# 2_MCU.net
KiCad netlist of a schematic drawn in Altium Designer
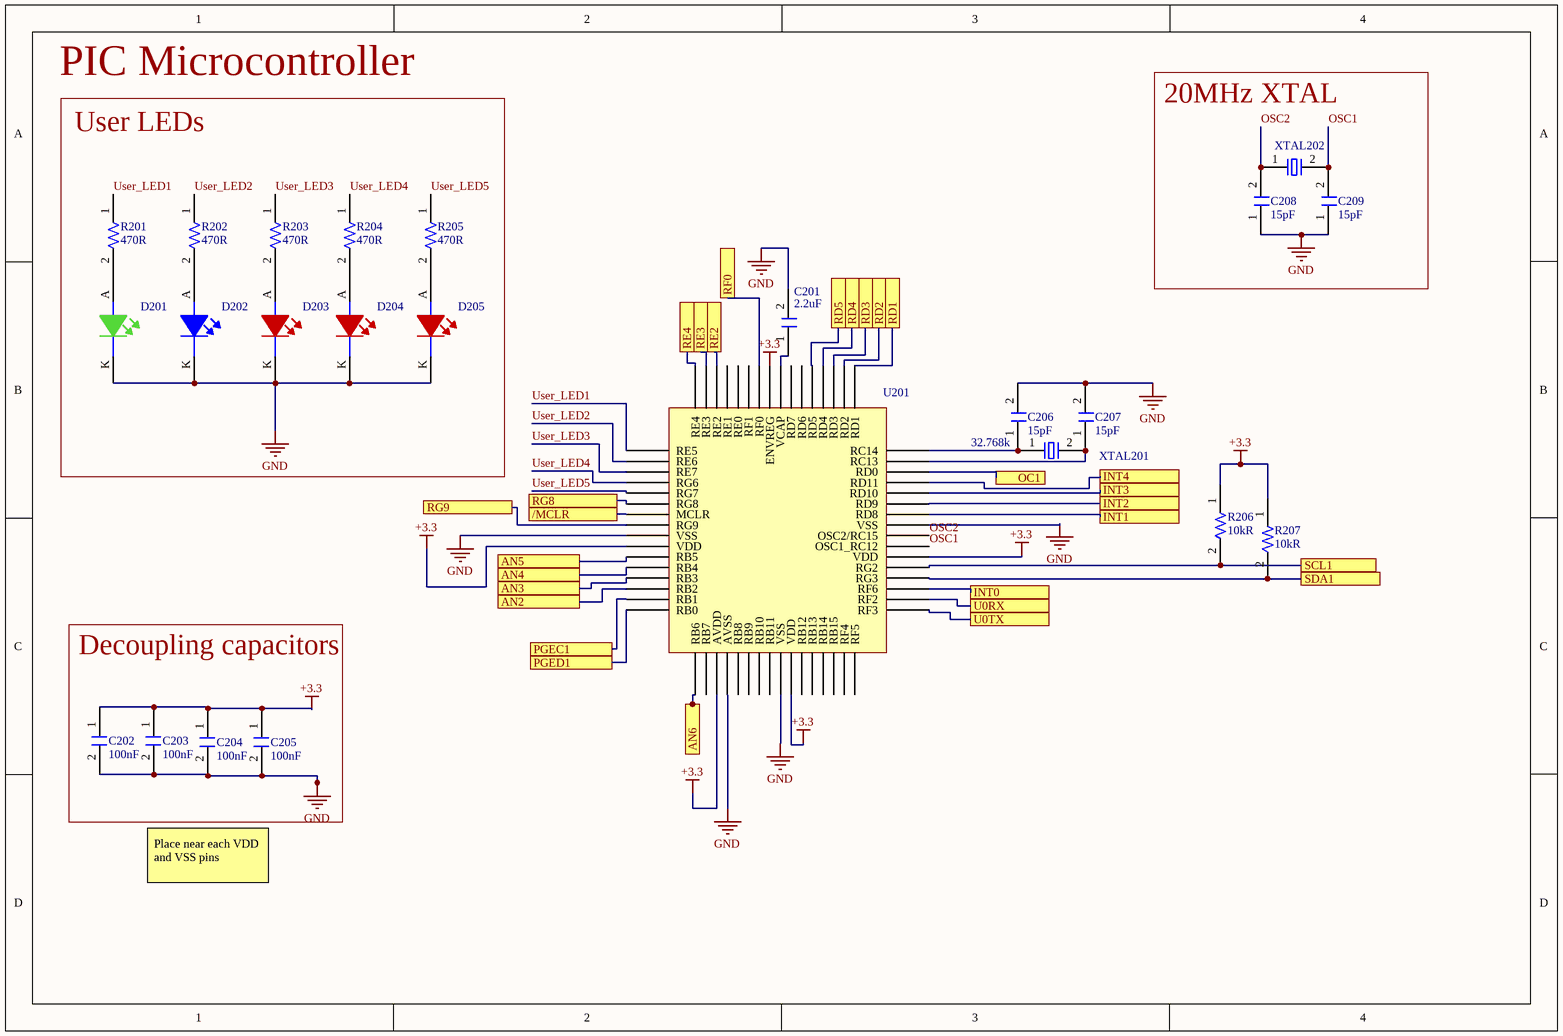
[diagram p0: [2]MCU.SchDoc]

(export (version "E")
  (design (tool "Eeschema 10.0.6"))
  (components
    (comp (ref "C201")
      (value "2.2uF")
      (footprint "C0805FNPC-W")
      (libsource (lib "Passives") (part "C2.2u-16V-0805FTK"))
    )
    (comp (ref "C202")
      (value "885012207098")
      (footprint "C0805FNPC-R")
      (description "Cap, 0.1ΜF, 50V, 10%, X7R, 0805")
      (fields
        (field (name "TOLERANCE") "10%")
        (field (name "CAPACITANCE") "100nF")
        (field (name ".CREATOR") "DR")
      )
      (libsource (lib "Passives") (part "C100n-50V-0805FNPC-X7R"))
    )
    (comp (ref "C203")
      (value "885012207098")
      (footprint "C0805FNPC-R")
      (description "Cap, 0.1ΜF, 50V, 10%, X7R, 0805")
      (fields
        (field (name "TOLERANCE") "10%")
        (field (name "CAPACITANCE") "100nF")
        (field (name ".CREATOR") "DR")
      )
      (libsource (lib "Passives") (part "C100n-50V-0805FNPC-X7R"))
    )
    (comp (ref "C204")
      (value "885012207098")
      (footprint "C0805FNPC-R")
      (description "Cap, 0.1ΜF, 50V, 10%, X7R, 0805")
      (fields
        (field (name "TOLERANCE") "10%")
        (field (name "CAPACITANCE") "100nF")
        (field (name ".CREATOR") "DR")
      )
      (libsource (lib "Passives") (part "C100n-50V-0805FNPC-X7R"))
    )
    (comp (ref "C205")
      (value "885012207098")
      (footprint "C0805FNPC-R")
      (description "Cap, 0.1ΜF, 50V, 10%, X7R, 0805")
      (fields
        (field (name "TOLERANCE") "10%")
        (field (name "CAPACITANCE") "100nF")
        (field (name ".CREATOR") "DR")
      )
      (libsource (lib "Passives") (part "C100n-50V-0805FNPC-X7R"))
    )
    (comp (ref "C206")
      (value "885012008038")
      (footprint "C1206FNPC-RW")
      (description "Cap, 15Pf, 50V, 5%, C0G/np0, 1206 Rohs Compliant: Yes")
      (fields
        (field (name "MANUFACTURER") "Wurth Electronics")
        (field (name "TOLERANCE") "5%")
        (field (name "CAPACITANCE") "15pF")
        (field (name ".CREATOR") "GP")
      )
      (libsource (lib "Passives") (part "C15p-50V-1206FNPC-NP0"))
    )
    (comp (ref "C207")
      (value "885012008038")
      (footprint "C1206FNPC-RW")
      (description "Cap, 15Pf, 50V, 5%, C0G/np0, 1206 Rohs Compliant: Yes")
      (fields
        (field (name "MANUFACTURER") "Wurth Electronics")
        (field (name "TOLERANCE") "5%")
        (field (name "CAPACITANCE") "15pF")
        (field (name ".CREATOR") "GP")
      )
      (libsource (lib "Passives") (part "C15p-50V-1206FNPC-NP0"))
    )
    (comp (ref "C208")
      (value "885012008038")
      (footprint "C1206FNPC-RW")
      (description "Cap, 15Pf, 50V, 5%, C0G/np0, 1206 Rohs Compliant: Yes")
      (fields
        (field (name "MANUFACTURER") "Wurth Electronics")
        (field (name "TOLERANCE") "5%")
        (field (name "CAPACITANCE") "15pF")
        (field (name ".CREATOR") "GP")
      )
      (libsource (lib "Passives") (part "C15p-50V-1206FNPC-NP0"))
    )
    (comp (ref "C209")
      (value "885012008038")
      (footprint "C1206FNPC-RW")
      (description "Cap, 15Pf, 50V, 5%, C0G/np0, 1206 Rohs Compliant: Yes")
      (fields
        (field (name "MANUFACTURER") "Wurth Electronics")
        (field (name "TOLERANCE") "5%")
        (field (name "CAPACITANCE") "15pF")
        (field (name ".CREATOR") "GP")
      )
      (libsource (lib "Passives") (part "C15p-50V-1206FNPC-NP0"))
    )
    (comp (ref "D201")
      (value "150080VS75000")
      (footprint "LED_0805_WE")
      (description "Led, Green, 570 Nm, 2 V, 30 Ma, 40 Mcd Rohs Compliant: Yes")
      (fields (field (name ".CREATOR") "DR"))
      (libsource (lib "Semiconductor") (part "LEDVS-0805-40"))
    )
    (comp (ref "D202")
      (value "150080BS75000")
      (footprint "LED_0805_WE")
      (description "LED BLUE CLEAR 0805 SMD")
      (fields (field (name ".CREATOR") "GP"))
      (libsource (lib "Semiconductor") (part "LEDBS-0805-145"))
    )
    (comp (ref "D203")
      (value "150080RS75000")
      (footprint "LED_0805_WE")
      (description "0805(H=0.8mm) 红色 高亮 λD=625nm VF=2V IF=30mA PD=72mW")
      (fields (field (name ".CREATOR") "DR"))
      (libsource (lib "Semiconductor") (part "LEDRS-0805-150"))
    )
    (comp (ref "D204")
      (value "150080RS75000")
      (footprint "LED_0805_WE")
      (description "0805(H=0.8mm) 红色 高亮 λD=625nm VF=2V IF=30mA PD=72mW")
      (fields (field (name ".CREATOR") "DR"))
      (libsource (lib "Semiconductor") (part "LEDRS-0805-150"))
    )
    (comp (ref "D205")
      (value "150080RS75000")
      (footprint "LED_0805_WE")
      (description "0805(H=0.8mm) 红色 高亮 λD=625nm VF=2V IF=30mA PD=72mW")
      (fields (field (name ".CREATOR") "DR"))
      (libsource (lib "Semiconductor") (part "LEDRS-0805-150"))
    )
    (comp (ref "R201")
      (value "CR0805-FX-4700GLF")
      (footprint "R0805FTK")
      (description "Res Thick Film 0805 470 Ohm 1% 1/8W ±100ppm/°C Molded SMD SMD Paper Tape on Plastic Reel")
      (fields
        (field (name "TOLERANCE") "1%")
        (field (name "RESISTANCE") "470R")
        (field (name ".CREATOR") "DR")
      )
      (libsource (lib "Passives") (part "R470-0805FTK"))
    )
    (comp (ref "R202")
      (value "CR0805-FX-4700GLF")
      (footprint "R0805FTK")
      (description "Res Thick Film 0805 470 Ohm 1% 1/8W ±100ppm/°C Molded SMD SMD Paper Tape on Plastic Reel")
      (fields
        (field (name "TOLERANCE") "1%")
        (field (name "RESISTANCE") "470R")
        (field (name ".CREATOR") "DR")
      )
      (libsource (lib "Passives") (part "R470-0805FTK"))
    )
    (comp (ref "R203")
      (value "CR0805-FX-4700GLF")
      (footprint "R0805FTK")
      (description "Res Thick Film 0805 470 Ohm 1% 1/8W ±100ppm/°C Molded SMD SMD Paper Tape on Plastic Reel")
      (fields
        (field (name "TOLERANCE") "1%")
        (field (name "RESISTANCE") "470R")
        (field (name ".CREATOR") "DR")
      )
      (libsource (lib "Passives") (part "R470-0805FTK"))
    )
    (comp (ref "R204")
      (value "CR0805-FX-4700GLF")
      (footprint "R0805FTK")
      (description "Res Thick Film 0805 470 Ohm 1% 1/8W ±100ppm/°C Molded SMD SMD Paper Tape on Plastic Reel")
      (fields
        (field (name "TOLERANCE") "1%")
        (field (name "RESISTANCE") "470R")
        (field (name ".CREATOR") "DR")
      )
      (libsource (lib "Passives") (part "R470-0805FTK"))
    )
    (comp (ref "R205")
      (value "CR0805-FX-4700GLF")
      (footprint "R0805FTK")
      (description "Res Thick Film 0805 470 Ohm 1% 1/8W ±100ppm/°C Molded SMD SMD Paper Tape on Plastic Reel")
      (fields
        (field (name "TOLERANCE") "1%")
        (field (name "RESISTANCE") "470R")
        (field (name ".CREATOR") "DR")
      )
      (libsource (lib "Passives") (part "R470-0805FTK"))
    )
    (comp (ref "R206")
      (value "CR0805-JW-103ELF")
      (footprint "R0805FTK")
      (fields
        (field (name "TOLERANCE") "5%")
        (field (name "RESISTANCE") "10kR")
        (field (name ".CREATOR") "DR")
      )
      (libsource (lib "Passives") (part "R10k-0805FTK"))
    )
    (comp (ref "R207")
      (value "CR0805-JW-103ELF")
      (footprint "R0805FTK")
      (fields
        (field (name "TOLERANCE") "5%")
        (field (name "RESISTANCE") "10kR")
        (field (name ".CREATOR") "DR")
      )
      (libsource (lib "Passives") (part "R10k-0805FTK"))
    )
    (comp (ref "U201")
      (value "PIC32MX340F512H")
      (footprint "QFP50P1200X1200X120_64N")
      (libsource (lib "CommonFiles_Library") (part "PIC32MX340F512H"))
    )
    (comp (ref "XTAL201")
      (value "32.768k")
      (footprint "XTAL_ABS06-32.768KHZ-9-T")
      (libsource (lib "CommonFiles_Library") (part "XTAL_SMD_32.768kHz"))
    )
    (comp (ref "XTAL202")
      (value "830028710")
      (footprint "XTAL20M_SMD")
      (description "830028710, 20 MHz")
      (fields (field (name "MANUFACTURER") "Würth Elektronik") (field (name ".CREATOR") "GP"))
      (libsource (lib "Passives") (part "XTAL20M_SMD"))
    )
  )
  (nets
    (net (code "1") (name "+3.3") (class "Default")
      (node (ref "C202") (pin "1") (pinfunction "1_1") (pintype "passive"))
      (node (ref "C203") (pin "1") (pinfunction "1_1") (pintype "passive"))
      (node (ref "C204") (pin "1") (pinfunction "1_1") (pintype "passive"))
      (node (ref "C205") (pin "1") (pinfunction "1_1") (pintype "passive"))
      (node (ref "R206") (pin "1") (pinfunction "1_1") (pintype "passive"))
      (node (ref "R207") (pin "1") (pinfunction "1_1") (pintype "passive"))
      (node (ref "U201") (pin "10") (pinfunction "VDD_10") (pintype "passive"))
      (node (ref "U201") (pin "19") (pinfunction "AVDD_19") (pintype "passive"))
      (node (ref "U201") (pin "26") (pinfunction "VDD_26") (pintype "passive"))
      (node (ref "U201") (pin "38") (pinfunction "VDD_38") (pintype "passive"))
      (node (ref "U201") (pin "57") (pinfunction "ENVREG_57") (pintype "passive"))
    )
    (net (code "2") (name "/AN2") (class "Default")
      (node (ref "U201") (pin "14") (pinfunction "RB2_14") (pintype "passive"))
    )
    (net (code "3") (name "/AN3") (class "Default")
      (node (ref "U201") (pin "13") (pinfunction "RB3_13") (pintype "passive"))
    )
    (net (code "4") (name "/AN4") (class "Default")
      (node (ref "U201") (pin "12") (pinfunction "RB4_12") (pintype "passive"))
    )
    (net (code "5") (name "/AN5") (class "Default")
      (node (ref "U201") (pin "11") (pinfunction "RB5_11") (pintype "passive"))
    )
    (net (code "6") (name "/AN6") (class "Default")
      (node (ref "U201") (pin "17") (pinfunction "RB6_17") (pintype "passive"))
    )
    (net (code "7") (name "/INT0") (class "Default")
      (node (ref "U201") (pin "35") (pinfunction "RF6_35") (pintype "passive"))
    )
    (net (code "8") (name "/INT1") (class "Default")
      (node (ref "U201") (pin "42") (pinfunction "RD8_42") (pintype "passive"))
    )
    (net (code "9") (name "/INT2") (class "Default")
      (node (ref "U201") (pin "43") (pinfunction "RD9_43") (pintype "passive"))
    )
    (net (code "10") (name "/INT3") (class "Default")
      (node (ref "U201") (pin "44") (pinfunction "RD10_44") (pintype "passive"))
    )
    (net (code "11") (name "/INT4") (class "Default")
      (node (ref "U201") (pin "45") (pinfunction "RD11_45") (pintype "passive"))
    )
    (net (code "12") (name "/OC1") (class "Default")
      (node (ref "U201") (pin "46") (pinfunction "RD0_46") (pintype "passive"))
    )
    (net (code "13") (name "/OSC1") (class "Default")
      (node (ref "C209") (pin "2") (pinfunction "2_2") (pintype "passive"))
      (node (ref "U201") (pin "39") (pinfunction "OSC1_RC12_39") (pintype "passive"))
      (node (ref "XTAL202") (pin "2") (pinfunction "2_2") (pintype "passive"))
    )
    (net (code "14") (name "/OSC2") (class "Default")
      (node (ref "C208") (pin "2") (pinfunction "2_2") (pintype "passive"))
      (node (ref "U201") (pin "40") (pinfunction "OSC2/RC15_40") (pintype "passive"))
      (node (ref "XTAL202") (pin "1") (pinfunction "1_1") (pintype "passive"))
    )
    (net (code "15") (name "/PGEC1") (class "Default")
      (node (ref "U201") (pin "15") (pinfunction "RB1_15") (pintype "passive"))
    )
    (net (code "16") (name "/PGED1") (class "Default")
      (node (ref "U201") (pin "16") (pinfunction "RB0_16") (pintype "passive"))
    )
    (net (code "17") (name "/RD1") (class "Default")
      (node (ref "U201") (pin "49") (pinfunction "RD1_49") (pintype "passive"))
    )
    (net (code "18") (name "/RD2") (class "Default")
      (node (ref "U201") (pin "50") (pinfunction "RD2_50") (pintype "passive"))
    )
    (net (code "19") (name "/RD3") (class "Default")
      (node (ref "U201") (pin "51") (pinfunction "RD3_51") (pintype "passive"))
    )
    (net (code "20") (name "/RD4") (class "Default")
      (node (ref "U201") (pin "52") (pinfunction "RD4_52") (pintype "passive"))
    )
    (net (code "21") (name "/RD5") (class "Default")
      (node (ref "U201") (pin "53") (pinfunction "RD5_53") (pintype "passive"))
    )
    (net (code "22") (name "/RE2") (class "Default")
      (node (ref "U201") (pin "62") (pinfunction "RE2_62") (pintype "passive"))
    )
    (net (code "23") (name "/RE3") (class "Default")
      (node (ref "U201") (pin "63") (pinfunction "RE3_63") (pintype "passive"))
    )
    (net (code "24") (name "/RE4") (class "Default")
      (node (ref "U201") (pin "64") (pinfunction "RE4_64") (pintype "passive"))
    )
    (net (code "25") (name "/RF0") (class "Default")
      (node (ref "U201") (pin "58") (pinfunction "RF0_58") (pintype "passive"))
    )
    (net (code "26") (name "/RG8") (class "Default")
      (node (ref "U201") (pin "6") (pinfunction "RG8_6") (pintype "passive"))
    )
    (net (code "27") (name "/RG9") (class "Default")
      (node (ref "U201") (pin "8") (pinfunction "RG9_8") (pintype "passive"))
    )
    (net (code "28") (name "/SCL1") (class "Default")
      (node (ref "R206") (pin "2") (pinfunction "2_2") (pintype "passive"))
      (node (ref "U201") (pin "37") (pinfunction "RG2_37") (pintype "passive"))
    )
    (net (code "29") (name "/SDA1") (class "Default")
      (node (ref "R207") (pin "2") (pinfunction "2_2") (pintype "passive"))
      (node (ref "U201") (pin "36") (pinfunction "RG3_36") (pintype "passive"))
    )
    (net (code "30") (name "/U0RX") (class "Default")
      (node (ref "U201") (pin "34") (pinfunction "RF2_34") (pintype "passive"))
    )
    (net (code "31") (name "/U0TX") (class "Default")
      (node (ref "U201") (pin "33") (pinfunction "RF3_33") (pintype "passive"))
    )
    (net (code "32") (name "/User_LED1") (class "Default")
      (node (ref "R201") (pin "1") (pinfunction "1_1") (pintype "passive"))
      (node (ref "U201") (pin "1") (pinfunction "RE5_1") (pintype "passive"))
    )
    (net (code "33") (name "/User_LED2") (class "Default")
      (node (ref "R202") (pin "1") (pinfunction "1_1") (pintype "passive"))
      (node (ref "U201") (pin "2") (pinfunction "RE6_2") (pintype "passive"))
    )
    (net (code "34") (name "/User_LED3") (class "Default")
      (node (ref "R203") (pin "1") (pinfunction "1_1") (pintype "passive"))
      (node (ref "U201") (pin "3") (pinfunction "RE7_3") (pintype "passive"))
    )
    (net (code "35") (name "/User_LED4") (class "Default")
      (node (ref "R204") (pin "1") (pinfunction "1_1") (pintype "passive"))
      (node (ref "U201") (pin "4") (pinfunction "RG6_4") (pintype "passive"))
    )
    (net (code "36") (name "/User_LED5") (class "Default")
      (node (ref "R205") (pin "1") (pinfunction "1_1") (pintype "passive"))
      (node (ref "U201") (pin "5") (pinfunction "RG7_5") (pintype "passive"))
    )
    (net (code "37") (name "/{slash}MCLR") (class "Default")
      (node (ref "U201") (pin "7") (pinfunction "MCLR_7") (pintype "passive"))
    )
    (net (code "38") (name "GND") (class "Default")
      (node (ref "C201") (pin "2") (pinfunction "2_2") (pintype "passive"))
      (node (ref "C202") (pin "2") (pinfunction "2_2") (pintype "passive"))
      (node (ref "C203") (pin "2") (pinfunction "2_2") (pintype "passive"))
      (node (ref "C204") (pin "2") (pinfunction "2_2") (pintype "passive"))
      (node (ref "C205") (pin "2") (pinfunction "2_2") (pintype "passive"))
      (node (ref "C206") (pin "2") (pinfunction "2_2") (pintype "passive"))
      (node (ref "C207") (pin "2") (pinfunction "2_2") (pintype "passive"))
      (node (ref "C208") (pin "1") (pinfunction "1_1") (pintype "passive"))
      (node (ref "C209") (pin "1") (pinfunction "1_1") (pintype "passive"))
      (node (ref "D201") (pin "K") (pinfunction "K_K") (pintype "passive"))
      (node (ref "D202") (pin "K") (pinfunction "K_K") (pintype "passive"))
      (node (ref "D203") (pin "K") (pinfunction "K_K") (pintype "passive"))
      (node (ref "D204") (pin "K") (pinfunction "K_K") (pintype "passive"))
      (node (ref "D205") (pin "K") (pinfunction "K_K") (pintype "passive"))
      (node (ref "U201") (pin "20") (pinfunction "AVSS_20") (pintype "passive"))
      (node (ref "U201") (pin "25") (pinfunction "VSS_25") (pintype "passive"))
      (node (ref "U201") (pin "41") (pinfunction "VSS_41") (pintype "passive"))
      (node (ref "U201") (pin "9") (pinfunction "VSS_9") (pintype "passive"))
    )
    (net (code "39") (name "Net-(D201-PadA)") (class "Default")
      (node (ref "D201") (pin "A") (pinfunction "A_A") (pintype "passive"))
      (node (ref "R201") (pin "2") (pinfunction "2_2") (pintype "passive"))
    )
    (net (code "40") (name "Net-(D202-PadA)") (class "Default")
      (node (ref "D202") (pin "A") (pinfunction "A_A") (pintype "passive"))
      (node (ref "R202") (pin "2") (pinfunction "2_2") (pintype "passive"))
    )
    (net (code "41") (name "Net-(D203-PadA)") (class "Default")
      (node (ref "D203") (pin "A") (pinfunction "A_A") (pintype "passive"))
      (node (ref "R203") (pin "2") (pinfunction "2_2") (pintype "passive"))
    )
    (net (code "42") (name "Net-(D204-PadA)") (class "Default")
      (node (ref "D204") (pin "A") (pinfunction "A_A") (pintype "passive"))
      (node (ref "R204") (pin "2") (pinfunction "2_2") (pintype "passive"))
    )
    (net (code "43") (name "Net-(D205-PadA)") (class "Default")
      (node (ref "D205") (pin "A") (pinfunction "A_A") (pintype "passive"))
      (node (ref "R205") (pin "2") (pinfunction "2_2") (pintype "passive"))
    )
    (net (code "44") (name "Net-(U201-RC13)") (class "Default")
      (node (ref "C207") (pin "1") (pinfunction "1_1") (pintype "passive"))
      (node (ref "U201") (pin "47") (pinfunction "RC13_47") (pintype "passive"))
      (node (ref "XTAL201") (pin "2") (pinfunction "2_2") (pintype "passive"))
    )
    (net (code "45") (name "Net-(U201-RC14)") (class "Default")
      (node (ref "C206") (pin "1") (pinfunction "1_1") (pintype "passive"))
      (node (ref "U201") (pin "48") (pinfunction "RC14_48") (pintype "passive"))
      (node (ref "XTAL201") (pin "1") (pinfunction "1_1") (pintype "passive"))
    )
    (net (code "46") (name "Net-(U201-VCAP)") (class "Default")
      (node (ref "C201") (pin "1") (pinfunction "1_1") (pintype "passive"))
      (node (ref "U201") (pin "56") (pinfunction "VCAP_56") (pintype "passive"))
    )
    (net (code "47") (name "unconnected-(U201-RB7-Pad18)") (class "Default")
      (node (ref "U201") (pin "18") (pinfunction "RB7_18") (pintype "passive"))
    )
    (net (code "48") (name "unconnected-(U201-RB8-Pad21)") (class "Default")
      (node (ref "U201") (pin "21") (pinfunction "RB8_21") (pintype "passive"))
    )
    (net (code "49") (name "unconnected-(U201-RB9-Pad22)") (class "Default")
      (node (ref "U201") (pin "22") (pinfunction "RB9_22") (pintype "passive"))
    )
    (net (code "50") (name "unconnected-(U201-RB10-Pad23)") (class "Default")
      (node (ref "U201") (pin "23") (pinfunction "RB10_23") (pintype "passive"))
    )
    (net (code "51") (name "unconnected-(U201-RB11-Pad24)") (class "Default")
      (node (ref "U201") (pin "24") (pinfunction "RB11_24") (pintype "passive"))
    )
    (net (code "52") (name "unconnected-(U201-RB12-Pad27)") (class "Default")
      (node (ref "U201") (pin "27") (pinfunction "RB12_27") (pintype "passive"))
    )
    (net (code "53") (name "unconnected-(U201-RB13-Pad28)") (class "Default")
      (node (ref "U201") (pin "28") (pinfunction "RB13_28") (pintype "passive"))
    )
    (net (code "54") (name "unconnected-(U201-RB14-Pad29)") (class "Default")
      (node (ref "U201") (pin "29") (pinfunction "RB14_29") (pintype "passive"))
    )
    (net (code "55") (name "unconnected-(U201-RB15-Pad30)") (class "Default")
      (node (ref "U201") (pin "30") (pinfunction "RB15_30") (pintype "passive"))
    )
    (net (code "56") (name "unconnected-(U201-RD6-Pad54)") (class "Default")
      (node (ref "U201") (pin "54") (pinfunction "RD6_54") (pintype "passive"))
    )
    (net (code "57") (name "unconnected-(U201-RD7-Pad55)") (class "Default")
      (node (ref "U201") (pin "55") (pinfunction "RD7_55") (pintype "passive"))
    )
    (net (code "58") (name "unconnected-(U201-RE0-Pad60)") (class "Default")
      (node (ref "U201") (pin "60") (pinfunction "RE0_60") (pintype "passive"))
    )
    (net (code "59") (name "unconnected-(U201-RE1-Pad61)") (class "Default")
      (node (ref "U201") (pin "61") (pinfunction "RE1_61") (pintype "passive"))
    )
    (net (code "60") (name "unconnected-(U201-RF1-Pad59)") (class "Default")
      (node (ref "U201") (pin "59") (pinfunction "RF1_59") (pintype "passive"))
    )
    (net (code "61") (name "unconnected-(U201-RF4-Pad31)") (class "Default")
      (node (ref "U201") (pin "31") (pinfunction "RF4_31") (pintype "passive"))
    )
    (net (code "62") (name "unconnected-(U201-RF5-Pad32)") (class "Default")
      (node (ref "U201") (pin "32") (pinfunction "RF5_32") (pintype "passive"))
    )
  )
)
